# 02_Sensor.net
KiCad netlist of a schematic drawn in Altium Designer
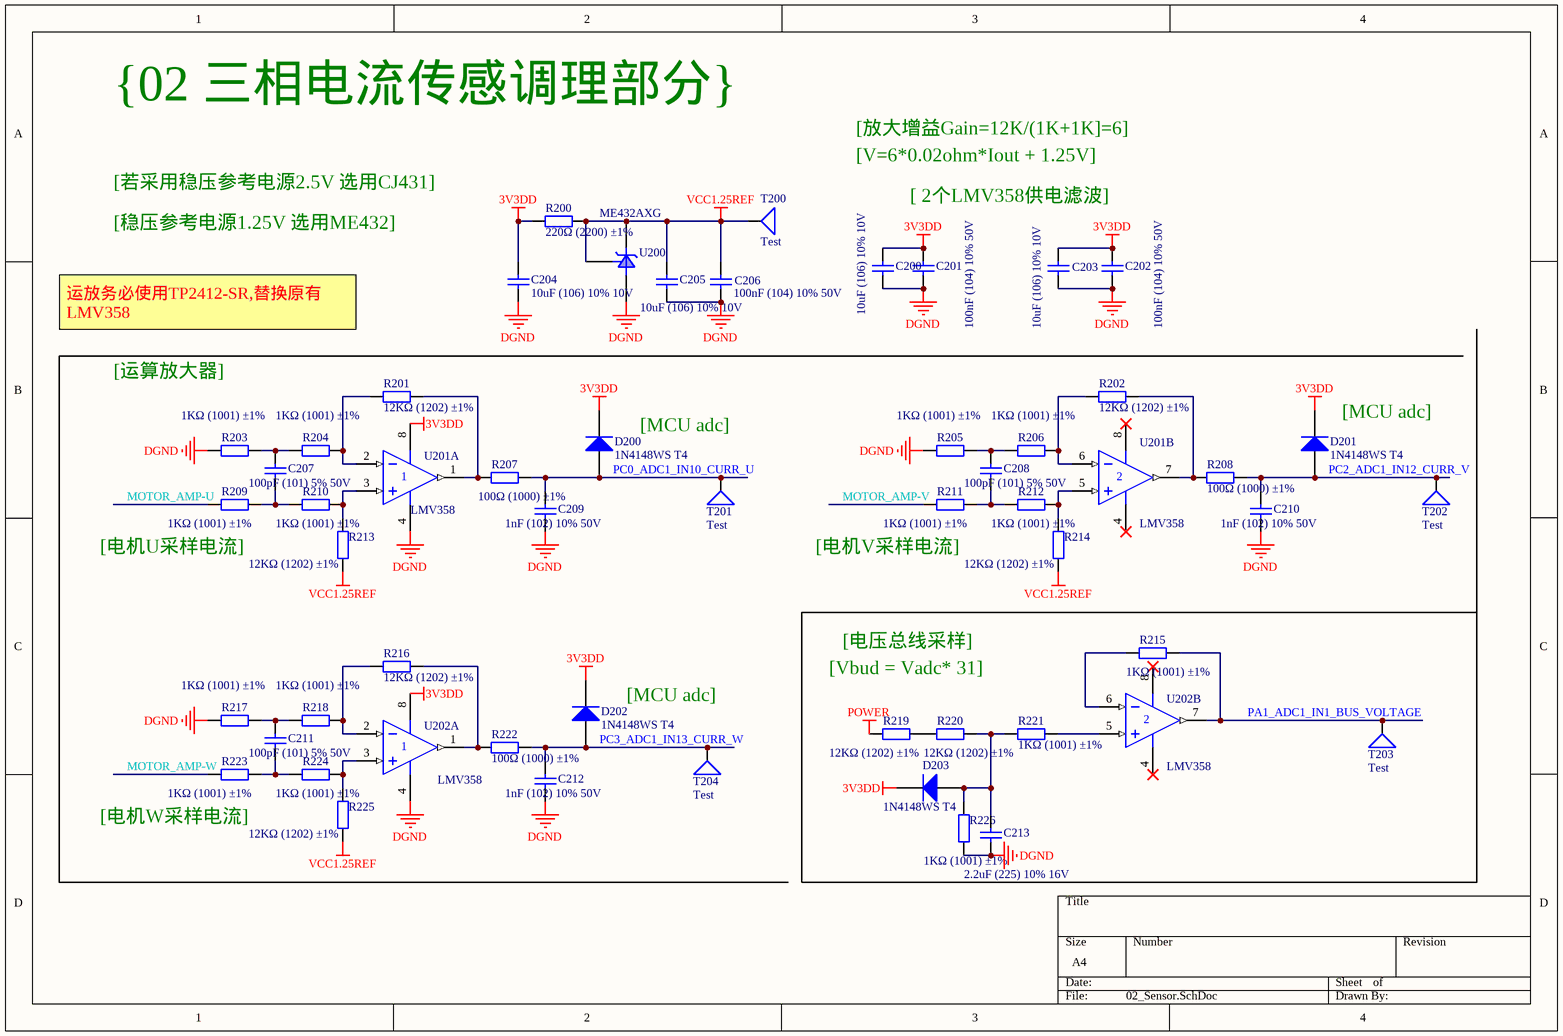
[diagram p0: 02_Sensor.SchDoc]

(export (version "E")
  (design (tool "Eeschema 10.0.6"))
  (components
    (comp (ref "C200")
      (value "10uF (106) 10% 10V")
      (footprint "LC-0603_C")
      (description "贴片电容")
      (libsource (lib "Miscellaneous Devices LC") (part "0603 10uF (106) 10% 10V"))
    )
    (comp (ref "C201")
      (value "100nF (104) 10% 50V")
      (footprint "LC-0603_C")
      (description "贴片电容")
      (libsource (lib "Miscellaneous Devices LC") (part "0603 100nF (104) 10% 50V"))
    )
    (comp (ref "C202")
      (value "100nF (104) 10% 50V")
      (footprint "LC-0603_C")
      (description "贴片电容")
      (libsource (lib "Miscellaneous Devices LC") (part "0603 100nF (104) 10% 50V"))
    )
    (comp (ref "C203")
      (value "10uF (106) 10% 10V")
      (footprint "LC-0603_C")
      (description "贴片电容")
      (libsource (lib "Miscellaneous Devices LC") (part "0603 10uF (106) 10% 10V"))
    )
    (comp (ref "C204")
      (value "10uF (106) 10% 10V")
      (footprint "LC-0603_C")
      (description "贴片电容")
      (libsource (lib "Miscellaneous Devices LC") (part "0603 10uF (106) 10% 10V"))
    )
    (comp (ref "C205")
      (value "10uF (106) 10% 10V")
      (footprint "LC-0603_C")
      (description "贴片电容")
      (libsource (lib "Miscellaneous Devices LC") (part "0603 10uF (106) 10% 10V"))
    )
    (comp (ref "C206")
      (value "100nF (104) 10% 50V")
      (footprint "LC-0603_C")
      (description "贴片电容")
      (libsource (lib "Miscellaneous Devices LC") (part "0603 100nF (104) 10% 50V"))
    )
    (comp (ref "C207")
      (value "100pF (101) 5% 50V")
      (footprint "LC-0603_C")
      (description "贴片电容")
      (libsource (lib "Miscellaneous Devices LC") (part "0603 100pF (101) 5% 50V"))
    )
    (comp (ref "C208")
      (value "100pF (101) 5% 50V")
      (footprint "LC-0603_C")
      (description "贴片电容")
      (libsource (lib "Miscellaneous Devices LC") (part "0603 100pF (101) 5% 50V"))
    )
    (comp (ref "C209")
      (value "1nF (102) 10% 50V")
      (footprint "LC-0603_C")
      (description "贴片电容")
      (libsource (lib "Miscellaneous Devices LC") (part "0603 1nF (102) 10% 50V"))
    )
    (comp (ref "C210")
      (value "1nF (102) 10% 50V")
      (footprint "LC-0603_C")
      (description "贴片电容")
      (libsource (lib "Miscellaneous Devices LC") (part "0603 1nF (102) 10% 50V"))
    )
    (comp (ref "C211")
      (value "100pF (101) 5% 50V")
      (footprint "LC-0603_C")
      (description "贴片电容")
      (libsource (lib "Miscellaneous Devices LC") (part "0603 100pF (101) 5% 50V"))
    )
    (comp (ref "C212")
      (value "1nF (102) 10% 50V")
      (footprint "LC-0603_C")
      (description "贴片电容")
      (libsource (lib "Miscellaneous Devices LC") (part "0603 1nF (102) 10% 50V"))
    )
    (comp (ref "C213")
      (value "2.2uF (225) 10% 16V")
      (footprint "LC-0603_C")
      (description "贴片电容")
      (libsource (lib "Miscellaneous Devices LC") (part "0603 2.2uF (225) 10% 16V"))
    )
    (comp (ref "D200")
      (value "1N4148WS T4")
      (footprint "LC-SOD-323")
      (description "二极管")
      (libsource (lib "Miscellaneous Devices LC") (part "SOD-323 1N4148WS T4"))
    )
    (comp (ref "D201")
      (value "1N4148WS T4")
      (footprint "LC-SOD-323")
      (description "二极管")
      (libsource (lib "Miscellaneous Devices LC") (part "SOD-323 1N4148WS T4"))
    )
    (comp (ref "D202")
      (value "1N4148WS T4")
      (footprint "LC-SOD-323")
      (description "二极管")
      (libsource (lib "Miscellaneous Devices LC") (part "SOD-323 1N4148WS T4"))
    )
    (comp (ref "D203")
      (value "1N4148WS T4")
      (footprint "LC-SOD-323")
      (description "二极管")
      (libsource (lib "Miscellaneous Devices LC") (part "SOD-323 1N4148WS T4"))
    )
    (comp (ref "R200")
      (value "220Ω (2200) ±1%")
      (footprint "LC-0603_R")
      (description "贴片电阻")
      (libsource (lib "Miscellaneous Devices LC") (part "0603 220Ω (2200) 1%"))
    )
    (comp (ref "R201")
      (value "12KΩ (1202) ±1%")
      (footprint "LC-0603_R")
      (description "贴片电阻")
      (libsource (lib "Miscellaneous Devices LC") (part "0603 12KΩ (1202) 1%"))
    )
    (comp (ref "R202")
      (value "12KΩ (1202) ±1%")
      (footprint "LC-0603_R")
      (description "贴片电阻")
      (libsource (lib "Miscellaneous Devices LC") (part "0603 12KΩ (1202) 1%"))
    )
    (comp (ref "R203")
      (value "1KΩ (1001) ±1%")
      (footprint "LC-0603_R")
      (description "贴片电阻")
      (libsource (lib "Miscellaneous Devices LC") (part "0603 1KΩ (1001) 1%"))
    )
    (comp (ref "R204")
      (value "1KΩ (1001) ±1%")
      (footprint "LC-0603_R")
      (description "贴片电阻")
      (libsource (lib "") (part "0603 1KΩ (1001) 1%_1"))
    )
    (comp (ref "R205")
      (value "1KΩ (1001) ±1%")
      (footprint "LC-0603_R")
      (description "贴片电阻")
      (libsource (lib "Miscellaneous Devices LC") (part "0603 1KΩ (1001) 1%"))
    )
    (comp (ref "R206")
      (value "1KΩ (1001) ±1%")
      (footprint "LC-0603_R")
      (description "贴片电阻")
      (libsource (lib "") (part "0603 1KΩ (1001) 1%_1"))
    )
    (comp (ref "R207")
      (value "100Ω (1000) ±1%")
      (footprint "LC-0603_R")
      (description "贴片电阻")
      (libsource (lib "Miscellaneous Devices LC") (part "0603 100Ω (1000) 1%"))
    )
    (comp (ref "R208")
      (value "100Ω (1000) ±1%")
      (footprint "LC-0603_R")
      (description "贴片电阻")
      (libsource (lib "Miscellaneous Devices LC") (part "0603 100Ω (1000) 1%"))
    )
    (comp (ref "R209")
      (value "1KΩ (1001) ±1%")
      (footprint "LC-0603_R")
      (description "贴片电阻")
      (libsource (lib "Miscellaneous Devices LC") (part "0603 1KΩ (1001) 1%"))
    )
    (comp (ref "R210")
      (value "1KΩ (1001) ±1%")
      (footprint "LC-0603_R")
      (description "贴片电阻")
      (libsource (lib "") (part "0603 1KΩ (1001) 1%_1"))
    )
    (comp (ref "R211")
      (value "1KΩ (1001) ±1%")
      (footprint "LC-0603_R")
      (description "贴片电阻")
      (libsource (lib "Miscellaneous Devices LC") (part "0603 1KΩ (1001) 1%"))
    )
    (comp (ref "R212")
      (value "1KΩ (1001) ±1%")
      (footprint "LC-0603_R")
      (description "贴片电阻")
      (libsource (lib "") (part "0603 1KΩ (1001) 1%_1"))
    )
    (comp (ref "R213")
      (value "12KΩ (1202) ±1%")
      (footprint "LC-0603_R")
      (description "贴片电阻")
      (libsource (lib "") (part "0603 12KΩ (1202) 1%_1"))
    )
    (comp (ref "R214")
      (value "12KΩ (1202) ±1%")
      (footprint "LC-0603_R")
      (description "贴片电阻")
      (libsource (lib "") (part "0603 12KΩ (1202) 1%_1"))
    )
    (comp (ref "R215")
      (value "1KΩ (1001) ±1%")
      (footprint "LC-0603_R")
      (description "贴片电阻")
      (libsource (lib "Miscellaneous Devices LC") (part "0603 1KΩ (1001) 1%"))
    )
    (comp (ref "R216")
      (value "12KΩ (1202) ±1%")
      (footprint "LC-0603_R")
      (description "贴片电阻")
      (libsource (lib "Miscellaneous Devices LC") (part "0603 12KΩ (1202) 1%"))
    )
    (comp (ref "R217")
      (value "1KΩ (1001) ±1%")
      (footprint "LC-0603_R")
      (description "贴片电阻")
      (libsource (lib "Miscellaneous Devices LC") (part "0603 1KΩ (1001) 1%"))
    )
    (comp (ref "R218")
      (value "1KΩ (1001) ±1%")
      (footprint "LC-0603_R")
      (description "贴片电阻")
      (libsource (lib "") (part "0603 1KΩ (1001) 1%_1"))
    )
    (comp (ref "R219")
      (value "12KΩ (1202) ±1%")
      (footprint "LC-0603_R")
      (description "贴片电阻")
      (libsource (lib "") (part "0603 12KΩ (1202) 1%_2"))
    )
    (comp (ref "R220")
      (value "12KΩ (1202) ±1%")
      (footprint "LC-0603_R")
      (description "贴片电阻")
      (libsource (lib "") (part "0603 12KΩ (1202) 1%_2"))
    )
    (comp (ref "R221")
      (value "1KΩ (1001) ±1%")
      (footprint "LC-0603_R")
      (description "贴片电阻")
      (libsource (lib "") (part "0603 1KΩ (1001) 1%_1"))
    )
    (comp (ref "R222")
      (value "100Ω (1000) ±1%")
      (footprint "LC-0603_R")
      (description "贴片电阻")
      (libsource (lib "Miscellaneous Devices LC") (part "0603 100Ω (1000) 1%"))
    )
    (comp (ref "R223")
      (value "1KΩ (1001) ±1%")
      (footprint "LC-0603_R")
      (description "贴片电阻")
      (libsource (lib "Miscellaneous Devices LC") (part "0603 1KΩ (1001) 1%"))
    )
    (comp (ref "R224")
      (value "1KΩ (1001) ±1%")
      (footprint "LC-0603_R")
      (description "贴片电阻")
      (libsource (lib "") (part "0603 1KΩ (1001) 1%_1"))
    )
    (comp (ref "R225")
      (value "12KΩ (1202) ±1%")
      (footprint "LC-0603_R")
      (description "贴片电阻")
      (libsource (lib "") (part "0603 12KΩ (1202) 1%_1"))
    )
    (comp (ref "R226")
      (value "1KΩ (1001) ±1%")
      (footprint "LC-0603_R")
      (description "贴片电阻")
      (libsource (lib "") (part "0603 1KΩ (1001) 1%_2"))
    )
    (comp (ref "T200")
      (value "Test")
      (footprint "Testpoint")
      (libsource (lib "RayPCB20210502") (part "TestPad"))
    )
    (comp (ref "T201")
      (value "Test")
      (footprint "Testpoint")
      (libsource (lib "RayPCB20210502") (part "TestPad"))
    )
    (comp (ref "T202")
      (value "Test")
      (footprint "Testpoint")
      (libsource (lib "RayPCB20210502") (part "TestPad"))
    )
    (comp (ref "T203")
      (value "Test")
      (footprint "Testpoint")
      (libsource (lib "RayPCB20210502") (part "TestPad"))
    )
    (comp (ref "T204")
      (value "Test")
      (footprint "Testpoint")
      (libsource (lib "RayPCB20210502") (part "TestPad"))
    )
    (comp (ref "U200")
      (value "ME432AXG")
      (footprint "LC-SOT-23(SOT-23-3)")
      (description "电压基准")
      (libsource (lib "Miscellaneous Devices LC") (part "CJ431 0.5%431"))
    )
    (comp (ref "U201")
      (value "LMV358")
      (footprint "TP2412-SR")
      (description "通用运放")
      (libsource (lib "Miscellaneous Devices LC") (part "LM358DR2G"))
    )
    (comp (ref "U202")
      (value "LMV358")
      (footprint "TP2412-SR")
      (description "通用运放")
      (libsource (lib "Miscellaneous Devices LC") (part "LM358DR2G"))
    )
  )
  (nets
    (net (code "1") (name "/MOTOR_AMP-U") (class "Default")
      (node (ref "R209") (pin "1") (pinfunction "1_1") (pintype "passive"))
    )
    (net (code "2") (name "/MOTOR_AMP-V") (class "Default")
      (node (ref "R211") (pin "1") (pinfunction "1_1") (pintype "passive"))
    )
    (net (code "3") (name "/MOTOR_AMP-W") (class "Default")
      (node (ref "R223") (pin "1") (pinfunction "1_1") (pintype "passive"))
    )
    (net (code "4") (name "/PA1_ADC1_IN1_BUS_VOLTAGE") (class "Default")
      (node (ref "R215") (pin "2") (pinfunction "2_2") (pintype "passive"))
      (node (ref "T203") (pin "1") (pinfunction "1_1") (pintype "passive"))
      (node (ref "U202") (pin "7") (pinfunction "OUT_7") (pintype "output"))
    )
    (net (code "5") (name "/PC0_ADC1_IN10_CURR_U") (class "Default")
      (node (ref "C209") (pin "2") (pinfunction "2_2") (pintype "passive"))
      (node (ref "D200") (pin "1") (pinfunction "A_1") (pintype "passive"))
      (node (ref "R207") (pin "2") (pinfunction "2_2") (pintype "passive"))
      (node (ref "T201") (pin "1") (pinfunction "1_1") (pintype "passive"))
    )
    (net (code "6") (name "/PC2_ADC1_IN12_CURR_V") (class "Default")
      (node (ref "C210") (pin "2") (pinfunction "2_2") (pintype "passive"))
      (node (ref "D201") (pin "1") (pinfunction "A_1") (pintype "passive"))
      (node (ref "R208") (pin "2") (pinfunction "2_2") (pintype "passive"))
      (node (ref "T202") (pin "1") (pinfunction "1_1") (pintype "passive"))
    )
    (net (code "7") (name "/PC3_ADC1_IN13_CURR_W") (class "Default")
      (node (ref "C212") (pin "2") (pinfunction "2_2") (pintype "passive"))
      (node (ref "D202") (pin "1") (pinfunction "A_1") (pintype "passive"))
      (node (ref "R222") (pin "2") (pinfunction "2_2") (pintype "passive"))
      (node (ref "T204") (pin "1") (pinfunction "1_1") (pintype "passive"))
    )
    (net (code "8") (name "3V3DD") (class "Default")
      (node (ref "C200") (pin "2") (pinfunction "2_2") (pintype "passive"))
      (node (ref "C201") (pin "2") (pinfunction "2_2") (pintype "passive"))
      (node (ref "C202") (pin "2") (pinfunction "2_2") (pintype "passive"))
      (node (ref "C203") (pin "2") (pinfunction "2_2") (pintype "passive"))
      (node (ref "C204") (pin "2") (pinfunction "2_2") (pintype "passive"))
      (node (ref "D200") (pin "2") (pinfunction "K_2") (pintype "passive"))
      (node (ref "D201") (pin "2") (pinfunction "K_2") (pintype "passive"))
      (node (ref "D202") (pin "2") (pinfunction "K_2") (pintype "passive"))
      (node (ref "D203") (pin "2") (pinfunction "K_2") (pintype "passive"))
      (node (ref "R200") (pin "1") (pinfunction "1_1") (pintype "passive"))
      (node (ref "U201") (pin "8") (pinfunction "V+_8") (pintype "power_in"))
      (node (ref "U202") (pin "8") (pinfunction "V+_8") (pintype "power_in"))
    )
    (net (code "9") (name "DGND") (class "Default")
      (node (ref "C200") (pin "1") (pinfunction "1_1") (pintype "passive"))
      (node (ref "C201") (pin "1") (pinfunction "1_1") (pintype "passive"))
      (node (ref "C202") (pin "1") (pinfunction "1_1") (pintype "passive"))
      (node (ref "C203") (pin "1") (pinfunction "1_1") (pintype "passive"))
      (node (ref "C204") (pin "1") (pinfunction "1_1") (pintype "passive"))
      (node (ref "C205") (pin "1") (pinfunction "1_1") (pintype "passive"))
      (node (ref "C206") (pin "1") (pinfunction "1_1") (pintype "passive"))
      (node (ref "C209") (pin "1") (pinfunction "1_1") (pintype "passive"))
      (node (ref "C210") (pin "1") (pinfunction "1_1") (pintype "passive"))
      (node (ref "C212") (pin "1") (pinfunction "1_1") (pintype "passive"))
      (node (ref "C213") (pin "1") (pinfunction "1_1") (pintype "passive"))
      (node (ref "R203") (pin "1") (pinfunction "1_1") (pintype "passive"))
      (node (ref "R205") (pin "1") (pinfunction "1_1") (pintype "passive"))
      (node (ref "R217") (pin "1") (pinfunction "1_1") (pintype "passive"))
      (node (ref "R226") (pin "1") (pinfunction "1_1") (pintype "passive"))
      (node (ref "U200") (pin "3") (pinfunction "A_3") (pintype "passive"))
      (node (ref "U201") (pin "4") (pinfunction "V-_4") (pintype "power_in"))
      (node (ref "U202") (pin "4") (pinfunction "V-_4") (pintype "power_in"))
    )
    (net (code "10") (name "Net-(C207-Pad1)") (class "Default")
      (node (ref "C207") (pin "1") (pinfunction "1_1") (pintype "passive"))
      (node (ref "R209") (pin "2") (pinfunction "2_2") (pintype "passive"))
      (node (ref "R210") (pin "2") (pinfunction "2_2") (pintype "passive"))
    )
    (net (code "11") (name "Net-(C207-Pad2)") (class "Default")
      (node (ref "C207") (pin "2") (pinfunction "2_2") (pintype "passive"))
      (node (ref "R203") (pin "2") (pinfunction "2_2") (pintype "passive"))
      (node (ref "R204") (pin "2") (pinfunction "2_2") (pintype "passive"))
    )
    (net (code "12") (name "Net-(C208-Pad1)") (class "Default")
      (node (ref "C208") (pin "1") (pinfunction "1_1") (pintype "passive"))
      (node (ref "R211") (pin "2") (pinfunction "2_2") (pintype "passive"))
      (node (ref "R212") (pin "2") (pinfunction "2_2") (pintype "passive"))
    )
    (net (code "13") (name "Net-(C208-Pad2)") (class "Default")
      (node (ref "C208") (pin "2") (pinfunction "2_2") (pintype "passive"))
      (node (ref "R205") (pin "2") (pinfunction "2_2") (pintype "passive"))
      (node (ref "R206") (pin "2") (pinfunction "2_2") (pintype "passive"))
    )
    (net (code "14") (name "Net-(C211-Pad1)") (class "Default")
      (node (ref "C211") (pin "1") (pinfunction "1_1") (pintype "passive"))
      (node (ref "R223") (pin "2") (pinfunction "2_2") (pintype "passive"))
      (node (ref "R224") (pin "2") (pinfunction "2_2") (pintype "passive"))
    )
    (net (code "15") (name "Net-(C211-Pad2)") (class "Default")
      (node (ref "C211") (pin "2") (pinfunction "2_2") (pintype "passive"))
      (node (ref "R217") (pin "2") (pinfunction "2_2") (pintype "passive"))
      (node (ref "R218") (pin "2") (pinfunction "2_2") (pintype "passive"))
    )
    (net (code "16") (name "Net-(D203-A)") (class "Default")
      (node (ref "C213") (pin "2") (pinfunction "2_2") (pintype "passive"))
      (node (ref "D203") (pin "1") (pinfunction "A_1") (pintype "passive"))
      (node (ref "R220") (pin "2") (pinfunction "2_2") (pintype "passive"))
      (node (ref "R221") (pin "2") (pinfunction "2_2") (pintype "passive"))
      (node (ref "R226") (pin "2") (pinfunction "2_2") (pintype "passive"))
    )
    (net (code "17") (name "Net-(R219-Pad2)") (class "Default")
      (node (ref "R219") (pin "2") (pinfunction "2_2") (pintype "passive"))
      (node (ref "R220") (pin "1") (pinfunction "1_1") (pintype "passive"))
    )
    (net (code "18") (name "Net-(U201A-IN+)") (class "Default")
      (node (ref "R210") (pin "1") (pinfunction "1_1") (pintype "passive"))
      (node (ref "R213") (pin "2") (pinfunction "2_2") (pintype "passive"))
      (node (ref "U201") (pin "3") (pinfunction "IN+_3") (pintype "input"))
    )
    (net (code "19") (name "Net-(U201A-IN-)") (class "Default")
      (node (ref "R201") (pin "2") (pinfunction "2_2") (pintype "passive"))
      (node (ref "R204") (pin "1") (pinfunction "1_1") (pintype "passive"))
      (node (ref "U201") (pin "2") (pinfunction "IN-_2") (pintype "input"))
    )
    (net (code "20") (name "Net-(U201A-OUT)") (class "Default")
      (node (ref "R201") (pin "1") (pinfunction "1_1") (pintype "passive"))
      (node (ref "R207") (pin "1") (pinfunction "1_1") (pintype "passive"))
      (node (ref "U201") (pin "1") (pinfunction "OUT_1") (pintype "output"))
    )
    (net (code "21") (name "Net-(U201B-IN+)") (class "Default")
      (node (ref "R212") (pin "1") (pinfunction "1_1") (pintype "passive"))
      (node (ref "R214") (pin "2") (pinfunction "2_2") (pintype "passive"))
      (node (ref "U201") (pin "5") (pinfunction "IN+_5") (pintype "input"))
    )
    (net (code "22") (name "Net-(U201B-IN-)") (class "Default")
      (node (ref "R202") (pin "2") (pinfunction "2_2") (pintype "passive"))
      (node (ref "R206") (pin "1") (pinfunction "1_1") (pintype "passive"))
      (node (ref "U201") (pin "6") (pinfunction "IN-_6") (pintype "input"))
    )
    (net (code "23") (name "Net-(U201B-OUT)") (class "Default")
      (node (ref "R202") (pin "1") (pinfunction "1_1") (pintype "passive"))
      (node (ref "R208") (pin "1") (pinfunction "1_1") (pintype "passive"))
      (node (ref "U201") (pin "7") (pinfunction "OUT_7") (pintype "output"))
    )
    (net (code "24") (name "Net-(U202A-IN+)") (class "Default")
      (node (ref "R224") (pin "1") (pinfunction "1_1") (pintype "passive"))
      (node (ref "R225") (pin "2") (pinfunction "2_2") (pintype "passive"))
      (node (ref "U202") (pin "3") (pinfunction "IN+_3") (pintype "input"))
    )
    (net (code "25") (name "Net-(U202A-IN-)") (class "Default")
      (node (ref "R216") (pin "2") (pinfunction "2_2") (pintype "passive"))
      (node (ref "R218") (pin "1") (pinfunction "1_1") (pintype "passive"))
      (node (ref "U202") (pin "2") (pinfunction "IN-_2") (pintype "input"))
    )
    (net (code "26") (name "Net-(U202A-OUT)") (class "Default")
      (node (ref "R216") (pin "1") (pinfunction "1_1") (pintype "passive"))
      (node (ref "R222") (pin "1") (pinfunction "1_1") (pintype "passive"))
      (node (ref "U202") (pin "1") (pinfunction "OUT_1") (pintype "output"))
    )
    (net (code "27") (name "Net-(U202B-IN+)") (class "Default")
      (node (ref "R221") (pin "1") (pinfunction "1_1") (pintype "passive"))
      (node (ref "U202") (pin "5") (pinfunction "IN+_5") (pintype "input"))
    )
    (net (code "28") (name "Net-(U202B-IN-)") (class "Default")
      (node (ref "R215") (pin "1") (pinfunction "1_1") (pintype "passive"))
      (node (ref "U202") (pin "6") (pinfunction "IN-_6") (pintype "input"))
    )
    (net (code "29") (name "POWER") (class "Default")
      (node (ref "R219") (pin "1") (pinfunction "1_1") (pintype "passive"))
    )
    (net (code "30") (name "VCC1.25REF") (class "Default")
      (node (ref "C205") (pin "2") (pinfunction "2_2") (pintype "passive"))
      (node (ref "C206") (pin "2") (pinfunction "2_2") (pintype "passive"))
      (node (ref "R200") (pin "2") (pinfunction "2_2") (pintype "passive"))
      (node (ref "R213") (pin "1") (pinfunction "1_1") (pintype "passive"))
      (node (ref "R214") (pin "1") (pinfunction "1_1") (pintype "passive"))
      (node (ref "R225") (pin "1") (pinfunction "1_1") (pintype "passive"))
      (node (ref "T200") (pin "1") (pinfunction "1_1") (pintype "passive"))
      (node (ref "U200") (pin "1") (pinfunction "R_1") (pintype "passive"))
      (node (ref "U200") (pin "2") (pinfunction "K_2") (pintype "passive"))
    )
    (net (code "31") (name "unconnected-(U201B-V+-Pad8)") (class "Default")
      (node (ref "U201") (pin "8") (pinfunction "V+_8") (pintype "power_in+no_connect"))
    )
    (net (code "32") (name "unconnected-(U201B-V--Pad4)") (class "Default")
      (node (ref "U201") (pin "4") (pinfunction "V-_4") (pintype "power_in+no_connect"))
    )
    (net (code "33") (name "unconnected-(U202B-V+-Pad8)") (class "Default")
      (node (ref "U202") (pin "8") (pinfunction "V+_8") (pintype "power_in+no_connect"))
    )
    (net (code "34") (name "unconnected-(U202B-V--Pad4)") (class "Default")
      (node (ref "U202") (pin "4") (pinfunction "V-_4") (pintype "power_in+no_connect"))
    )
  )
)
